# SNES_USB-C.net
KiCad netlist of a schematic drawn in EAGLE
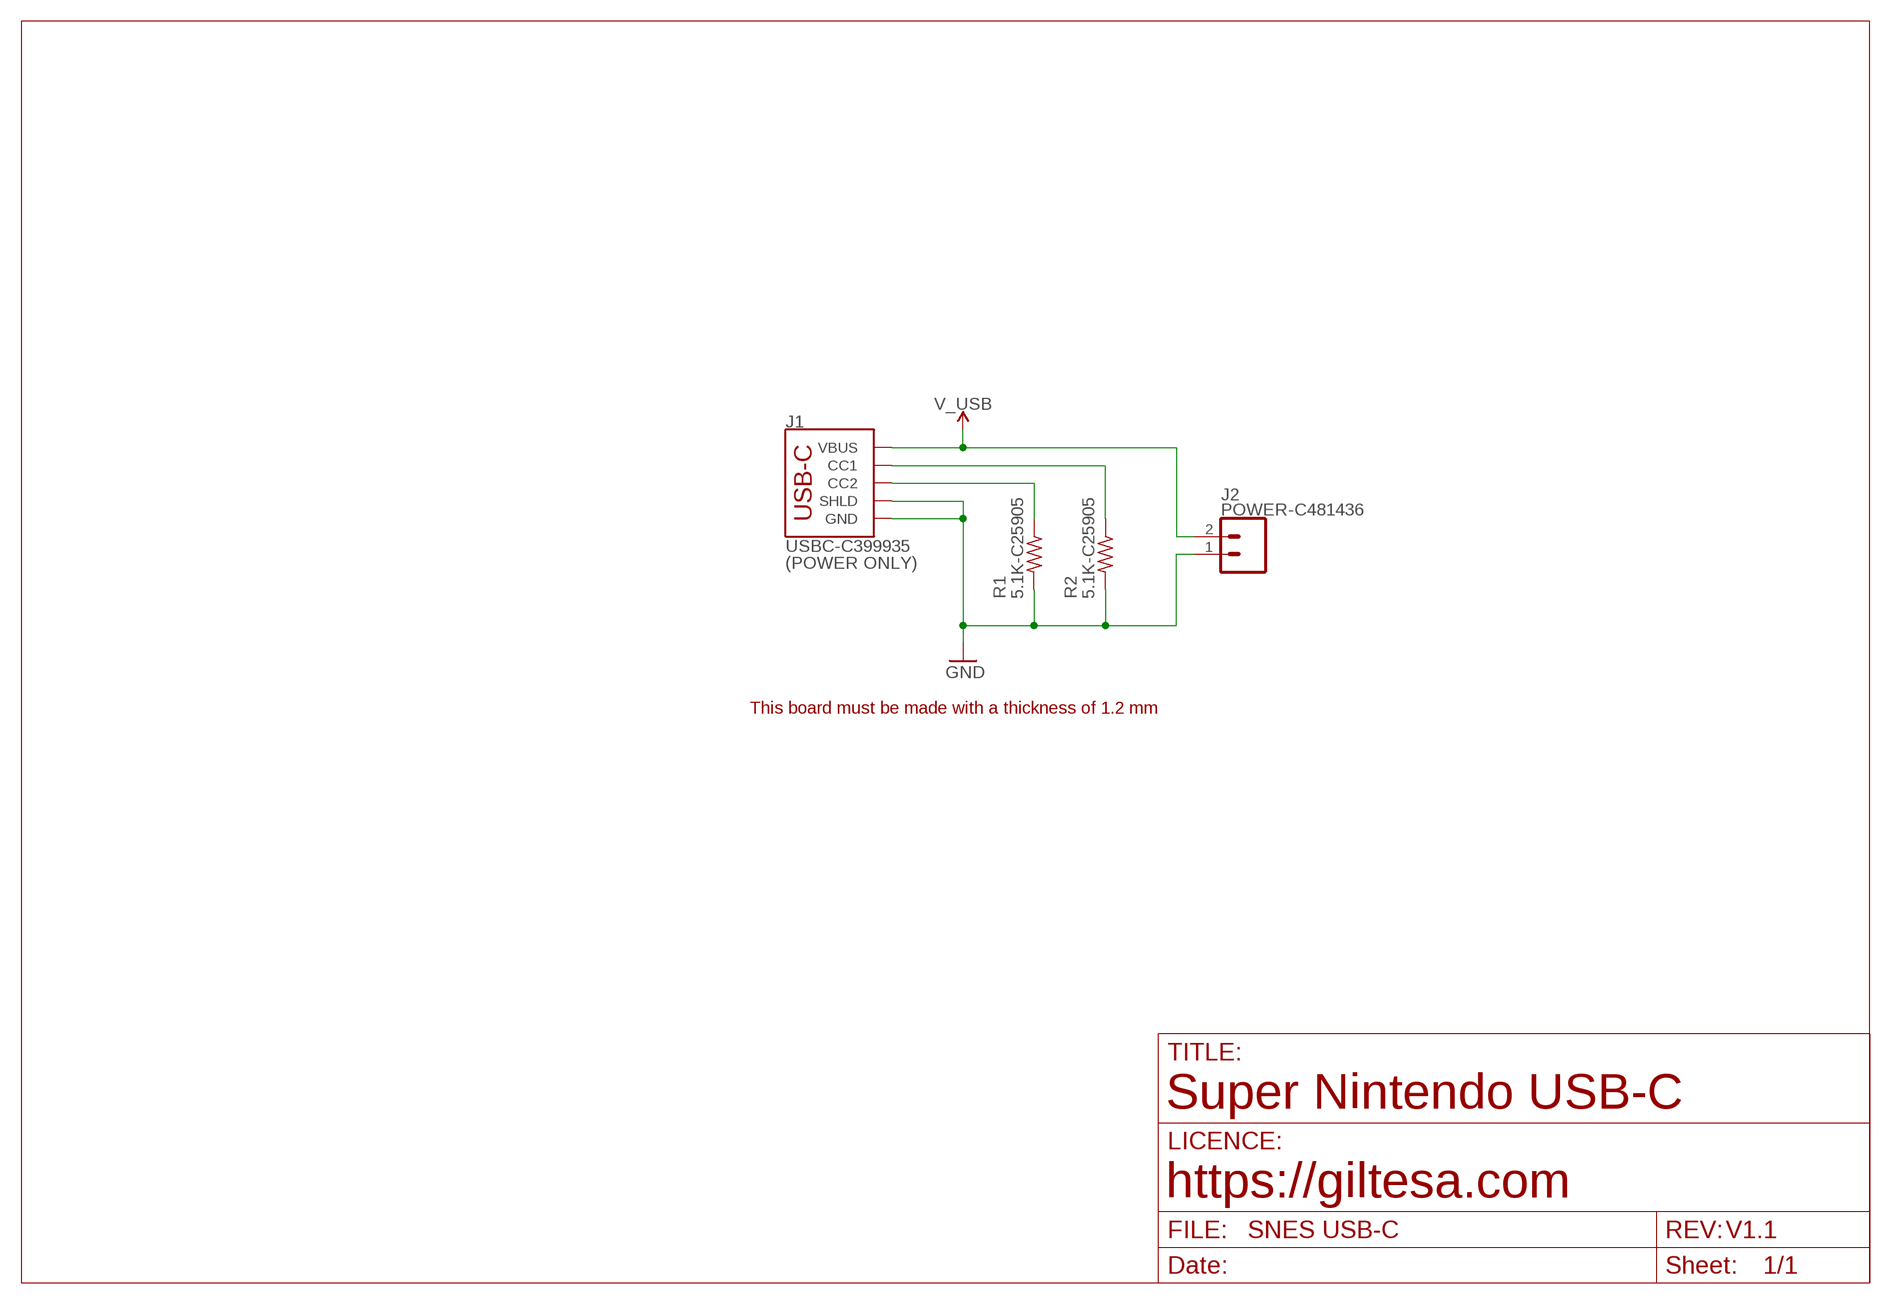
[diagram p0: schematic, sheet 1]

(export (version "E")
  (design (tool "Eeschema 10.0.6"))
  (components
    (comp (ref "J1")
      (value "USBC-C399935")
      (footprint "eagle-import:USB-C_6P_SIDE")
      (libsource (lib "eagle-import") (part "USB-C_6P_POWER_SIDE"))
    )
    (comp (ref "J2")
      (value "POWER-C481436")
      (footprint "eagle-import:JST-2-1.25MM_RIGHT")
      (libsource (lib "eagle-import") (part "JST-2_1.25MM"))
    )
    (comp (ref "R1")
      (value "5.1K-C25905")
      (footprint "eagle-import:R0402")
      (libsource (lib "eagle-import") (part "R0402"))
    )
    (comp (ref "R2")
      (value "5.1K-C25905")
      (footprint "eagle-import:R0402")
      (libsource (lib "eagle-import") (part "R0402"))
    )
  )
  (nets
    (net (code "1") (name "GND") (class "Default")
      (node (ref "J1") (pin "A12-GND") (pinfunction "GND_A12-GND") (pintype "bidirectional"))
      (node (ref "J1") (pin "B12-GND") (pinfunction "GND_B12-GND") (pintype "bidirectional"))
      (node (ref "J1") (pin "SHLD1") (pinfunction "SHLD_SHLD1") (pintype "bidirectional"))
      (node (ref "J1") (pin "SHLD2") (pinfunction "SHLD_SHLD2") (pintype "bidirectional"))
      (node (ref "J1") (pin "SHLD3") (pinfunction "SHLD_SHLD3") (pintype "bidirectional"))
      (node (ref "J1") (pin "SHLD4") (pinfunction "SHLD_SHLD4") (pintype "bidirectional"))
      (node (ref "J2") (pin "1") (pinfunction "1_1") (pintype "passive"))
      (node (ref "R1") (pin "2") (pinfunction "2_2") (pintype "passive"))
      (node (ref "R2") (pin "2") (pinfunction "2_2") (pintype "passive"))
    )
    (net (code "2") (name "Net-(J1-CC1)") (class "Default")
      (node (ref "J1") (pin "A5") (pinfunction "CC1_A5") (pintype "bidirectional"))
      (node (ref "R2") (pin "1") (pinfunction "1_1") (pintype "passive"))
    )
    (net (code "3") (name "Net-(J1-CC2)") (class "Default")
      (node (ref "J1") (pin "B5") (pinfunction "CC2_B5") (pintype "bidirectional"))
      (node (ref "R1") (pin "1") (pinfunction "1_1") (pintype "passive"))
    )
    (net (code "4") (name "V_USB") (class "Default")
      (node (ref "J1") (pin "A9-VBUS") (pinfunction "VBUS_A9-VBUS") (pintype "bidirectional"))
      (node (ref "J1") (pin "B9-VBUS") (pinfunction "VBUS_B9-VBUS") (pintype "bidirectional"))
      (node (ref "J2") (pin "2") (pinfunction "2_2") (pintype "passive"))
    )
  )
)
